# InputBuffer.net
KiCad netlist of a schematic drawn in Altium Designer
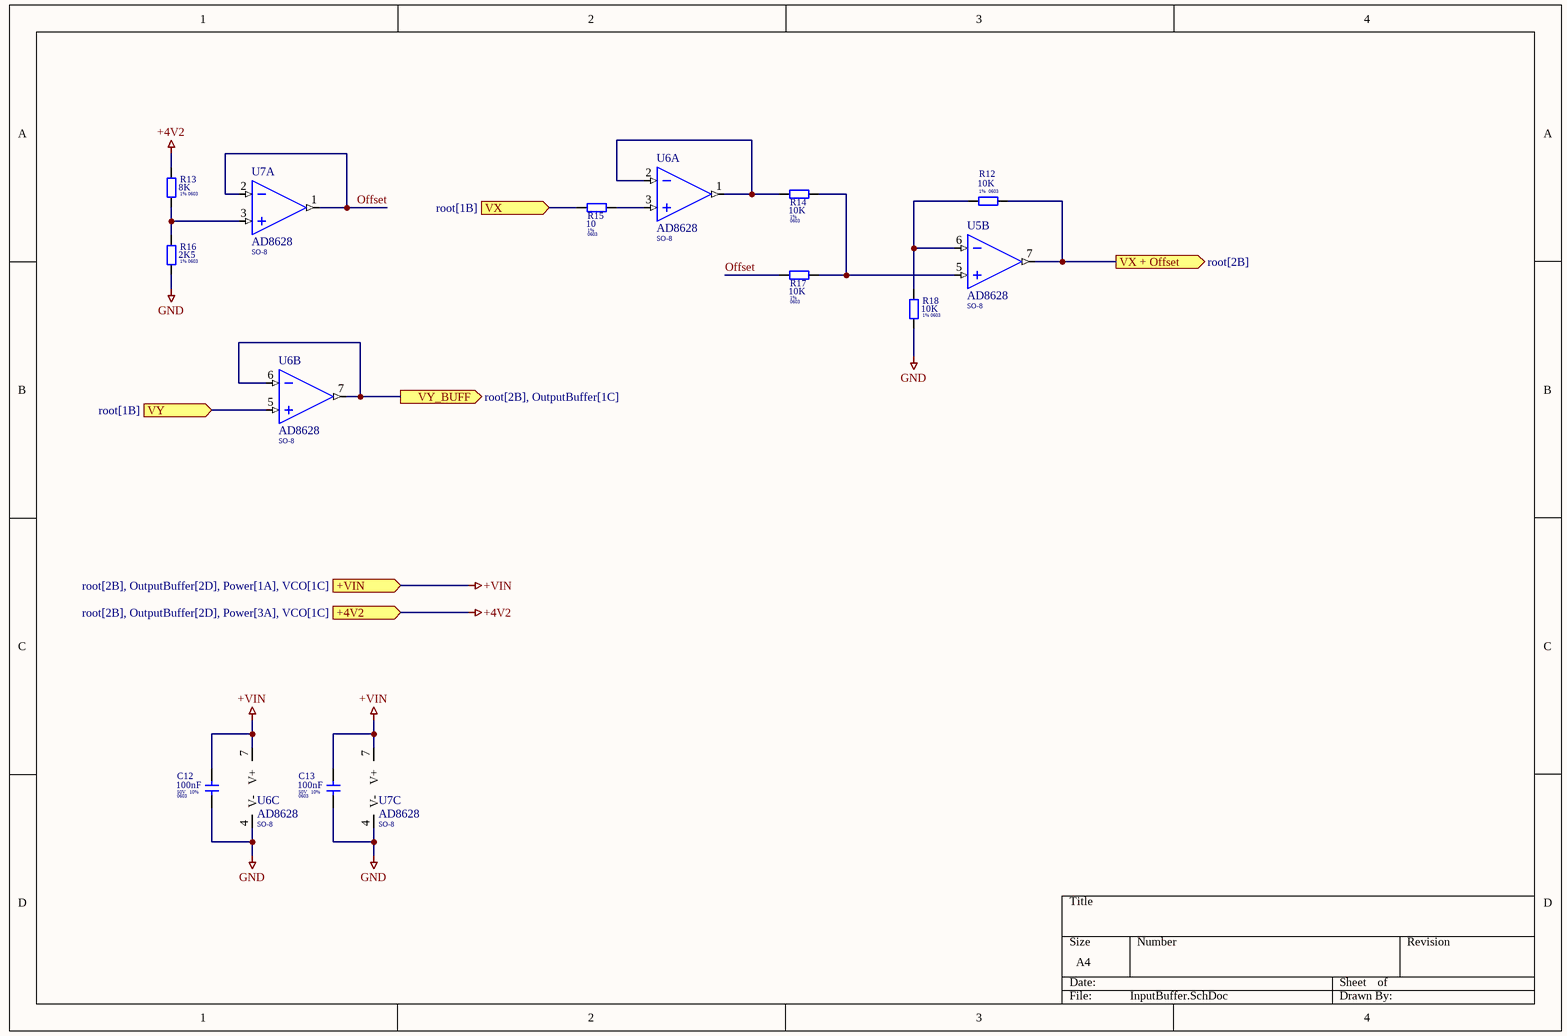
[diagram p0: InputBuffer.SchDoc]

(export (version "E")
  (design (tool "Eeschema 10.0.6"))
  (components
    (comp (ref "C12")
      (value "100nF")
      (footprint "CAPC1608X06M")
      (fields
        (field (name "VOLTAGE") "50V")
        (field (name "TOLERANT") "10%")
        (field (name "PACKAGE") "0603")
        (field (name "Comment") "100nF/50V")
      )
      (libsource (lib "Falcon-SchMain-Lib") (part "C"))
    )
    (comp (ref "C13")
      (value "100nF")
      (footprint "CAPC1608X06M")
      (fields
        (field (name "VOLTAGE") "50V")
        (field (name "TOLERANT") "10%")
        (field (name "PACKAGE") "0603")
        (field (name "Comment") "100nF/50V")
      )
      (libsource (lib "Falcon-SchMain-Lib") (part "C"))
    )
    (comp (ref "R12")
      (value "10K")
      (footprint "RESC1608X06L")
      (fields
        (field (name "PACKAGE") "0603")
        (field (name "TOLERANCE") "1%")
        (field (name "Comment") "10K 1%")
      )
      (libsource (lib "") (part "R_1"))
    )
    (comp (ref "R13")
      (value "8K")
      (footprint "RESC1608X06L")
      (fields
        (field (name "PACKAGE") "0603")
        (field (name "TOLERANCE") "1%")
        (field (name "Comment") "8K 1%")
      )
      (libsource (lib "Falcon-SchMain-Lib") (part "R"))
    )
    (comp (ref "R14")
      (value "10K")
      (footprint "RESC1608X06L")
      (fields
        (field (name "PACKAGE") "0603")
        (field (name "TOLERANCE") "1%")
        (field (name "Comment") "10K 1%")
      )
      (libsource (lib "") (part "R_1"))
    )
    (comp (ref "R15")
      (value "10")
      (footprint "RESC1608X06L")
      (fields
        (field (name "PACKAGE") "0603")
        (field (name "TOLERANCE") "1%")
        (field (name "Comment") "10 1%")
      )
      (libsource (lib "") (part "R_1"))
    )
    (comp (ref "R16")
      (value "2K5")
      (footprint "RESC1608X06L")
      (fields
        (field (name "PACKAGE") "0603")
        (field (name "TOLERANCE") "1%")
        (field (name "Comment") "2K5 1%")
      )
      (libsource (lib "Falcon-SchMain-Lib") (part "R"))
    )
    (comp (ref "R17")
      (value "10K")
      (footprint "RESC1608X06L")
      (fields
        (field (name "PACKAGE") "0603")
        (field (name "TOLERANCE") "1%")
        (field (name "Comment") "10K 1%")
      )
      (libsource (lib "") (part "R_1"))
    )
    (comp (ref "R18")
      (value "10K")
      (footprint "RESC1608X06L")
      (fields
        (field (name "PACKAGE") "0603")
        (field (name "TOLERANCE") "1%")
        (field (name "Comment") "10K 1%")
      )
      (libsource (lib "Falcon-SchMain-Lib") (part "R"))
    )
    (comp (ref "U5")
      (value "AD8628")
      (footprint "SOIC127P600X170-8N")
      (description "Zero-Drift, Single-Supply, Rail-to-Rail Input/Output Operational Amplifier")
      (fields (field (name "PACKAGE") "SO-8"))
      (libsource (lib "Falcon-SchMain-Lib") (part "AD8628ARZ"))
    )
    (comp (ref "U6")
      (value "AD8628")
      (footprint "SOIC127P600X170-8N")
      (description "Zero-Drift, Single-Supply, Rail-to-Rail Input/Output Operational Amplifier")
      (fields (field (name "PACKAGE") "SO-8"))
      (libsource (lib "Falcon-SchMain-Lib") (part "AD8628ARZ"))
    )
    (comp (ref "U7")
      (value "AD8628")
      (footprint "SOIC127P600X170-8N")
      (description "Zero-Drift, Single-Supply, Rail-to-Rail Input/Output Operational Amplifier")
      (fields (field (name "PACKAGE") "SO-8"))
      (libsource (lib "Falcon-SchMain-Lib") (part "AD8628ARZ"))
    )
  )
  (nets
    (net (code "1") (name "+4V2") (class "Default")
      (node (ref "R13") (pin "2") (pinfunction "2_2") (pintype "passive"))
    )
    (net (code "2") (name "+VIN") (class "Default")
      (node (ref "C12") (pin "2") (pinfunction "2_2") (pintype "passive"))
      (node (ref "C13") (pin "2") (pinfunction "2_2") (pintype "passive"))
      (node (ref "U6") (pin "7") (pinfunction "V+_7") (pintype "power_in"))
      (node (ref "U7") (pin "7") (pinfunction "V+_7") (pintype "power_in"))
    )
    (net (code "3") (name "/Offset") (class "Default")
      (node (ref "R17") (pin "1") (pinfunction "1_1") (pintype "passive"))
      (node (ref "U7") (pin "1") (pinfunction "OUT_1") (pintype "output"))
      (node (ref "U7") (pin "2") (pinfunction "IN-_2") (pintype "input"))
    )
    (net (code "4") (name "/VX") (class "Default")
      (node (ref "R15") (pin "1") (pinfunction "1_1") (pintype "passive"))
    )
    (net (code "5") (name "/VX + Offset") (class "Default")
      (node (ref "R12") (pin "2") (pinfunction "2_2") (pintype "passive"))
      (node (ref "U5") (pin "7") (pinfunction "OUT_7") (pintype "output"))
    )
    (net (code "6") (name "/VY") (class "Default")
      (node (ref "U6") (pin "5") (pinfunction "IN+_5") (pintype "input"))
    )
    (net (code "7") (name "/VY_BUFF") (class "Default")
      (node (ref "U6") (pin "6") (pinfunction "IN-_6") (pintype "input"))
      (node (ref "U6") (pin "7") (pinfunction "OUT_7") (pintype "output"))
    )
    (net (code "8") (name "GND") (class "Default")
      (node (ref "C12") (pin "1") (pinfunction "1_1") (pintype "passive"))
      (node (ref "C13") (pin "1") (pinfunction "1_1") (pintype "passive"))
      (node (ref "R16") (pin "1") (pinfunction "1_1") (pintype "passive"))
      (node (ref "R18") (pin "1") (pinfunction "1_1") (pintype "passive"))
      (node (ref "U6") (pin "4") (pinfunction "V-_4") (pintype "power_in"))
      (node (ref "U7") (pin "4") (pinfunction "V-_4") (pintype "power_in"))
    )
    (net (code "9") (name "Net-(U5B-IN+)") (class "Default")
      (node (ref "R14") (pin "2") (pinfunction "2_2") (pintype "passive"))
      (node (ref "R17") (pin "2") (pinfunction "2_2") (pintype "passive"))
      (node (ref "U5") (pin "5") (pinfunction "IN+_5") (pintype "input"))
    )
    (net (code "10") (name "Net-(U5B-IN-)") (class "Default")
      (node (ref "R12") (pin "1") (pinfunction "1_1") (pintype "passive"))
      (node (ref "R18") (pin "2") (pinfunction "2_2") (pintype "passive"))
      (node (ref "U5") (pin "6") (pinfunction "IN-_6") (pintype "input"))
    )
    (net (code "11") (name "Net-(U6A-IN+)") (class "Default")
      (node (ref "R15") (pin "2") (pinfunction "2_2") (pintype "passive"))
      (node (ref "U6") (pin "3") (pinfunction "IN+_3") (pintype "input"))
    )
    (net (code "12") (name "Net-(U6A-IN-)") (class "Default")
      (node (ref "R14") (pin "1") (pinfunction "1_1") (pintype "passive"))
      (node (ref "U6") (pin "1") (pinfunction "OUT_1") (pintype "output"))
      (node (ref "U6") (pin "2") (pinfunction "IN-_2") (pintype "input"))
    )
    (net (code "13") (name "Net-(U7A-IN+)") (class "Default")
      (node (ref "R13") (pin "1") (pinfunction "1_1") (pintype "passive"))
      (node (ref "R16") (pin "2") (pinfunction "2_2") (pintype "passive"))
      (node (ref "U7") (pin "3") (pinfunction "IN+_3") (pintype "input"))
    )
  )
)
